# apex-alpha-ii-aaa-version.net
KiCad netlist of a schematic drawn in EAGLE
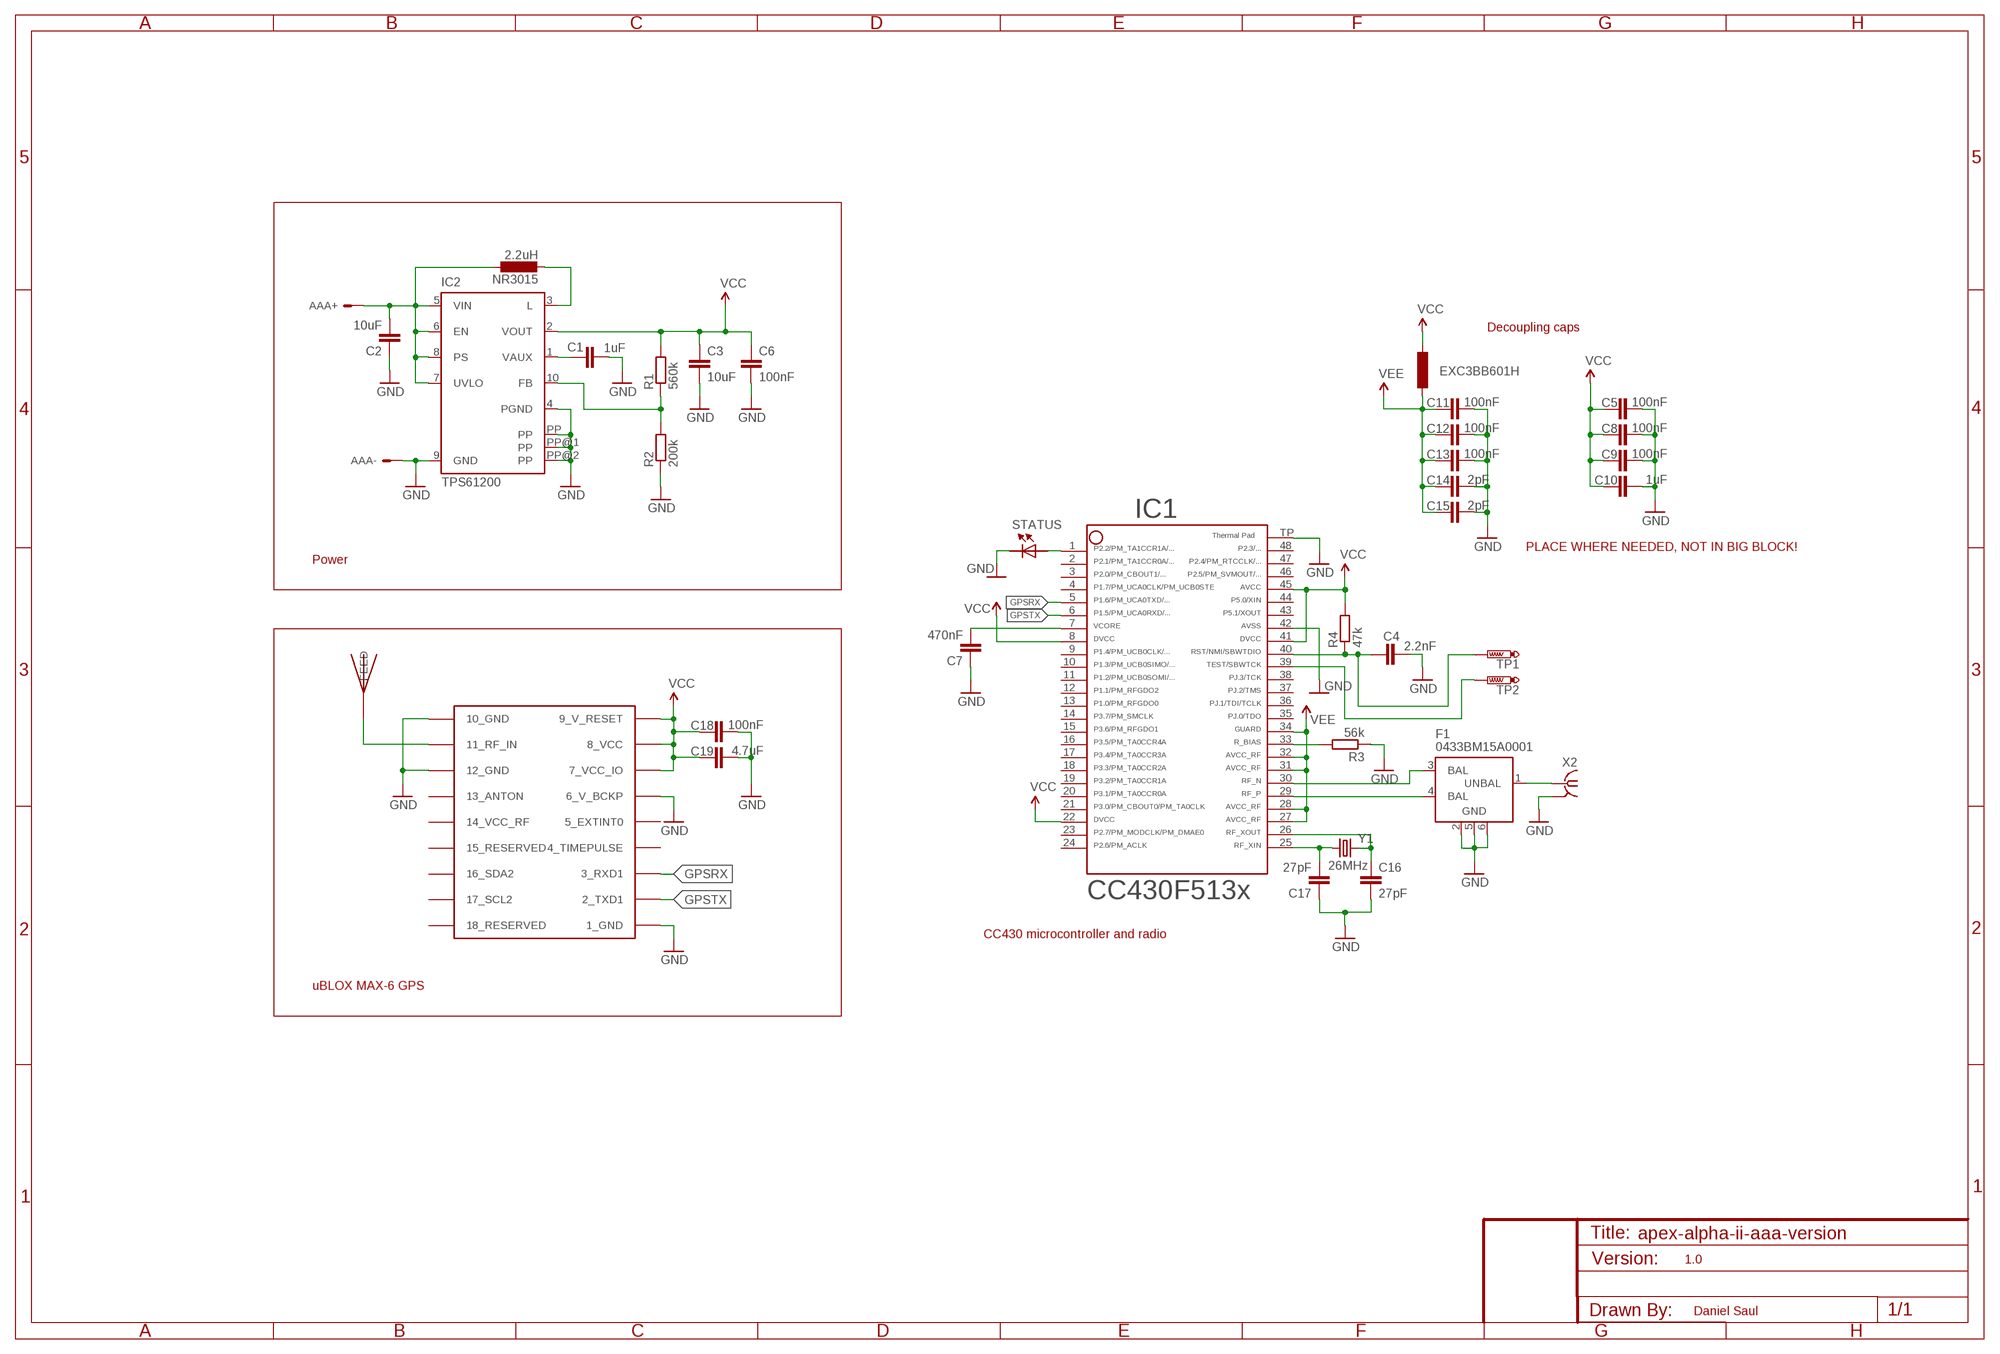
[diagram p0: schematic, sheet 1]

(export (version "E")
  (design (tool "Eeschema 10.0.6"))
  (components
    (comp (ref "AAA")
      (value "KEYSTONE-2466-THROUGH-HOLE-BATTERY-HOLDER-AAA")
      (footprint "eagle-import:THROUGH-HOLE-BATTERY-HOLDER-AAA")
      (libsource (lib "eagle-import") (part "KEYSTONE-2466-THROUGH-HOLE-BATTERY-HOLDER-AAA"))
    )
    (comp (ref "C1")
      (value "1uF")
      (footprint "eagle-import:0402-CAP")
      (libsource (lib "eagle-import") (part "CAP0402-CAP"))
    )
    (comp (ref "C2")
      (value "10uF")
      (footprint "eagle-import:0805")
      (libsource (lib "eagle-import") (part "CAP0805"))
    )
    (comp (ref "C3")
      (value "10uF")
      (footprint "eagle-import:0805")
      (libsource (lib "eagle-import") (part "CAP0805"))
    )
    (comp (ref "C4")
      (value "2.2nF")
      (footprint "eagle-import:0402-CAP")
      (libsource (lib "eagle-import") (part "CAP0402-CAP"))
    )
    (comp (ref "C5")
      (value "100nF")
      (footprint "eagle-import:0402-CAP")
      (libsource (lib "eagle-import") (part "CAP0402-CAP"))
    )
    (comp (ref "C6")
      (value "100nF")
      (footprint "eagle-import:0402-CAP")
      (libsource (lib "eagle-import") (part "CAP0402-CAP"))
    )
    (comp (ref "C7")
      (value "470nF")
      (footprint "eagle-import:0402-CAP")
      (libsource (lib "eagle-import") (part "CAP0402-CAP"))
    )
    (comp (ref "C8")
      (value "100nF")
      (footprint "eagle-import:0402-CAP")
      (libsource (lib "eagle-import") (part "CAP0402-CAP"))
    )
    (comp (ref "C9")
      (value "100nF")
      (footprint "eagle-import:0402-CAP")
      (libsource (lib "eagle-import") (part "CAP0402-CAP"))
    )
    (comp (ref "C10")
      (value "1uF")
      (footprint "eagle-import:0402-CAP")
      (libsource (lib "eagle-import") (part "CAP0402-CAP"))
    )
    (comp (ref "C11")
      (value "100nF")
      (footprint "eagle-import:0402-CAP")
      (libsource (lib "eagle-import") (part "CAP0402-CAP"))
    )
    (comp (ref "C12")
      (value "100nF")
      (footprint "eagle-import:0402-CAP")
      (libsource (lib "eagle-import") (part "CAP0402-CAP"))
    )
    (comp (ref "C13")
      (value "100nF")
      (footprint "eagle-import:0402-CAP")
      (libsource (lib "eagle-import") (part "CAP0402-CAP"))
    )
    (comp (ref "C14")
      (value "2pF")
      (footprint "eagle-import:0402-CAP")
      (libsource (lib "eagle-import") (part "CAP0402-CAP"))
    )
    (comp (ref "C15")
      (value "2pF")
      (footprint "eagle-import:0402-CAP")
      (libsource (lib "eagle-import") (part "CAP0402-CAP"))
    )
    (comp (ref "C16")
      (value "27pF")
      (footprint "eagle-import:0402-CAP")
      (libsource (lib "eagle-import") (part "CAP0402-CAP"))
    )
    (comp (ref "C17")
      (value "27pF")
      (footprint "eagle-import:0402-CAP")
      (libsource (lib "eagle-import") (part "CAP0402-CAP"))
    )
    (comp (ref "C18")
      (value "100nF")
      (footprint "eagle-import:0402-CAP")
      (libsource (lib "eagle-import") (part "CAP0402-CAP"))
    )
    (comp (ref "C19")
      (value "4.7uF")
      (footprint "eagle-import:0805")
      (libsource (lib "eagle-import") (part "CAP0805"))
    )
    (comp (ref "F1")
      (value "0433BM15A0001")
      (footprint "eagle-import:2450BM15A0002")
      (libsource (lib "eagle-import") (part "2450BM15A0002"))
    )
    (comp (ref "GPS")
      (value "UBLOX_MAX-6")
      (footprint "eagle-import:UBLOX_MAX-6")
      (libsource (lib "eagle-import") (part "UBLOX_MAX-6"))
    )
    (comp (ref "IC1")
      (value "CC430F5135")
      (footprint "eagle-import:RGZ48")
      (libsource (lib "eagle-import") (part "CC430F513X---RGZ48"))
    )
    (comp (ref "IC2")
      (value "TPS61200")
      (footprint "eagle-import:S-PDSO-N10")
      (fields (field (name "MPN") "TPS61200DRCT"))
      (libsource (lib "eagle-import") (part "TPS61200"))
    )
    (comp (ref "NR3015")
      (value "2.2uH")
      (footprint "eagle-import:NR3015")
      (libsource (lib "eagle-import") (part "NR3015"))
    )
    (comp (ref "R1")
      (value "560k")
      (footprint "eagle-import:R0402")
      (libsource (lib "eagle-import") (part "R-EU_R0402"))
    )
    (comp (ref "R2")
      (value "200k")
      (footprint "eagle-import:R0402")
      (libsource (lib "eagle-import") (part "R-EU_R0402"))
    )
    (comp (ref "R3")
      (value "56k")
      (footprint "eagle-import:R0402")
      (libsource (lib "eagle-import") (part "R-EU_R0402"))
    )
    (comp (ref "R4")
      (value "47k")
      (footprint "eagle-import:R0402")
      (libsource (lib "eagle-import") (part "R-EU_R0402"))
    )
    (comp (ref "TP1")
      (value "PTR1B1,27")
      (footprint "eagle-import:B1,27")
      (libsource (lib "eagle-import") (part "PTR1B1,27"))
    )
    (comp (ref "TP2")
      (value "PTR1B1,27")
      (footprint "eagle-import:B1,27")
      (libsource (lib "eagle-import") (part "PTR1B1,27"))
    )
    (comp (ref "U$1")
      (value "JTI_ANTENNA-1575AT43A40")
      (footprint "eagle-import:JTI_ANTENNA-1575AT43A40")
      (libsource (lib "eagle-import") (part "JTI_ANTENNA-1575AT43A40"))
    )
    (comp (ref "U$2")
      (value "EXC3BB601H")
      (footprint "eagle-import:R0603")
      (libsource (lib "eagle-import") (part "0603INDUCTOR"))
    )
    (comp (ref "U$3")
      (value "STATUS")
      (footprint "eagle-import:R0402")
      (libsource (lib "eagle-import") (part "LED"))
    )
    (comp (ref "X2")
      (value "SMA-142-0701-801/806")
      (footprint "eagle-import:J502-ND-142-0701-801_806")
      (fields
        (field (name "MF") "JOHNSON COMPONENTS")
        (field (name "MPN") "142-0701-801")
        (field (name "MPN_1") "142-0701-801")
        (field (name "OC_FARNELL") "1608592")
        (field (name "OC_NEWARK") "90F2624")
      )
      (libsource (lib "eagle-import") (part "SMA-142-0701-801/806"))
    )
    (comp (ref "Y1")
      (value "26MHz")
      (footprint "eagle-import:CRYSTAL-SMD-5X3")
      (libsource (lib "eagle-import") (part "CRYSTAL5X3"))
    )
  )
  (nets
    (net (code "1") (name "GND") (class "Default")
      (node (ref "AAA") (pin "GND") (pinfunction "S_GND") (pintype "passive"))
      (node (ref "C1") (pin "2") (pinfunction "2_2") (pintype "passive"))
      (node (ref "C10") (pin "2") (pinfunction "2_2") (pintype "passive"))
      (node (ref "C11") (pin "2") (pinfunction "2_2") (pintype "passive"))
      (node (ref "C12") (pin "2") (pinfunction "2_2") (pintype "passive"))
      (node (ref "C13") (pin "2") (pinfunction "2_2") (pintype "passive"))
      (node (ref "C14") (pin "2") (pinfunction "2_2") (pintype "passive"))
      (node (ref "C15") (pin "2") (pinfunction "2_2") (pintype "passive"))
      (node (ref "C16") (pin "2") (pinfunction "2_2") (pintype "passive"))
      (node (ref "C17") (pin "1") (pinfunction "1_1") (pintype "passive"))
      (node (ref "C18") (pin "2") (pinfunction "2_2") (pintype "passive"))
      (node (ref "C19") (pin "2") (pinfunction "2_2") (pintype "passive"))
      (node (ref "C2") (pin "1") (pinfunction "1_1") (pintype "passive"))
      (node (ref "C3") (pin "2") (pinfunction "2_2") (pintype "passive"))
      (node (ref "C4") (pin "2") (pinfunction "2_2") (pintype "passive"))
      (node (ref "C5") (pin "2") (pinfunction "2_2") (pintype "passive"))
      (node (ref "C6") (pin "2") (pinfunction "2_2") (pintype "passive"))
      (node (ref "C7") (pin "1") (pinfunction "1_1") (pintype "passive"))
      (node (ref "C8") (pin "2") (pinfunction "2_2") (pintype "passive"))
      (node (ref "C9") (pin "2") (pinfunction "2_2") (pintype "passive"))
      (node (ref "F1") (pin "2") (pinfunction "GND_2") (pintype "passive"))
      (node (ref "F1") (pin "5") (pinfunction "GND_5") (pintype "passive"))
      (node (ref "F1") (pin "6") (pinfunction "GND_6") (pintype "passive"))
      (node (ref "GPS") (pin "10_GND") (pinfunction "10_GND_10_GND") (pintype "power_in"))
      (node (ref "GPS") (pin "12_GND") (pinfunction "12_GND_12_GND") (pintype "power_in"))
      (node (ref "GPS") (pin "1_GND") (pinfunction "1_GND_1_GND") (pintype "power_in"))
      (node (ref "GPS") (pin "6_V_BCKP") (pinfunction "6_V_BCKP_6_V_BCKP") (pintype "bidirectional"))
      (node (ref "IC1") (pin "42") (pinfunction "42_42") (pintype "power_in"))
      (node (ref "IC1") (pin "TP") (pinfunction "49_TP") (pintype "power_in"))
      (node (ref "IC2") (pin "4") (pinfunction "PGND_4") (pintype "power_in"))
      (node (ref "IC2") (pin "9") (pinfunction "GND_9") (pintype "power_in"))
      (node (ref "IC2") (pin "PP") (pinfunction "PP_PP") (pintype "power_in"))
      (node (ref "IC2") (pin "PP@1") (pinfunction "PP_PP@1") (pintype "power_in"))
      (node (ref "IC2") (pin "PP@2") (pinfunction "PP_PP@2") (pintype "power_in"))
      (node (ref "R2") (pin "1") (pinfunction "1_1") (pintype "passive"))
      (node (ref "R3") (pin "1") (pinfunction "1_1") (pintype "passive"))
      (node (ref "U$3") (pin "1") (pinfunction "C_1") (pintype "passive"))
      (node (ref "X2") (pin "G@1") (pinfunction "GND_G@1") (pintype "power_in"))
    )
    (net (code "2") (name "GPSRX") (class "Default")
      (node (ref "GPS") (pin "3_RXD1") (pinfunction "3_RXD1_3_RXD1") (pintype "bidirectional"))
      (node (ref "IC1") (pin "5") (pinfunction "5_5") (pintype "bidirectional"))
    )
    (net (code "3") (name "GPSTX") (class "Default")
      (node (ref "GPS") (pin "2_TXD1") (pinfunction "2_TXD1_2_TXD1") (pintype "bidirectional"))
      (node (ref "IC1") (pin "6") (pinfunction "6_6") (pintype "bidirectional"))
    )
    (net (code "4") (name "Net-(AAAA-S)") (class "Default")
      (node (ref "AAA") (pin "+V") (pinfunction "S_+V") (pintype "passive"))
      (node (ref "C2") (pin "2") (pinfunction "2_2") (pintype "passive"))
      (node (ref "IC2") (pin "5") (pinfunction "VIN_5") (pintype "input"))
      (node (ref "IC2") (pin "6") (pinfunction "EN_6") (pintype "input"))
      (node (ref "IC2") (pin "7") (pinfunction "UVLO_7") (pintype "input"))
      (node (ref "IC2") (pin "8") (pinfunction "PS_8") (pintype "input"))
      (node (ref "NR3015") (pin "P$1") (pinfunction "1_P$1") (pintype "passive"))
    )
    (net (code "5") (name "Net-(C4-Pad1)") (class "Default")
      (node (ref "C4") (pin "1") (pinfunction "1_1") (pintype "passive"))
      (node (ref "IC1") (pin "40") (pinfunction "40_40") (pintype "bidirectional"))
      (node (ref "R4") (pin "1") (pinfunction "1_1") (pintype "passive"))
      (node (ref "TP1") (pin "TP") (pinfunction "TP_TP") (pintype "input"))
    )
    (net (code "6") (name "Net-(C7-Pad2)") (class "Default")
      (node (ref "C7") (pin "2") (pinfunction "2_2") (pintype "passive"))
      (node (ref "IC1") (pin "7") (pinfunction "7_7") (pintype "power_in"))
    )
    (net (code "7") (name "Net-(C17-Pad2)") (class "Default")
      (node (ref "C17") (pin "2") (pinfunction "2_2") (pintype "passive"))
      (node (ref "IC1") (pin "25") (pinfunction "25_25") (pintype "input"))
      (node (ref "Y1") (pin "1") (pinfunction "1_1") (pintype "passive"))
    )
    (net (code "8") (name "Net-(F1-BAL-Pad3)") (class "Default")
      (node (ref "F1") (pin "3") (pinfunction "BAL_3") (pintype "passive"))
      (node (ref "IC1") (pin "30") (pinfunction "30_30") (pintype "bidirectional"))
    )
    (net (code "9") (name "Net-(F1-BAL-Pad4)") (class "Default")
      (node (ref "F1") (pin "4") (pinfunction "BAL_4") (pintype "passive"))
      (node (ref "IC1") (pin "29") (pinfunction "29_29") (pintype "bidirectional"))
    )
    (net (code "10") (name "Net-(F1-UNBAL)") (class "Default")
      (node (ref "F1") (pin "1") (pinfunction "UNBAL_1") (pintype "passive"))
      (node (ref "X2") (pin "1") (pinfunction "1_1") (pintype "passive"))
    )
    (net (code "11") (name "Net-(GPS-Pad11_RF_IN)") (class "Default")
      (node (ref "GPS") (pin "11_RF_IN") (pinfunction "11_RF_IN_11_RF_IN") (pintype "bidirectional"))
      (node (ref "U$1") (pin "FEED") (pinfunction "FEED_FEED") (pintype "bidirectional"))
    )
    (net (code "12") (name "Net-(IC1-Pad33)") (class "Default")
      (node (ref "IC1") (pin "33") (pinfunction "33_33") (pintype "power_in"))
      (node (ref "R3") (pin "2") (pinfunction "2_2") (pintype "passive"))
    )
    (net (code "13") (name "Net-(IC1-Pad39)") (class "Default")
      (node (ref "IC1") (pin "39") (pinfunction "39_39") (pintype "input"))
      (node (ref "TP2") (pin "TP") (pinfunction "TP_TP") (pintype "input"))
    )
    (net (code "14") (name "Net-(IC2-FB)") (class "Default")
      (node (ref "IC2") (pin "10") (pinfunction "FB_10") (pintype "input"))
      (node (ref "R1") (pin "1") (pinfunction "1_1") (pintype "passive"))
      (node (ref "R2") (pin "2") (pinfunction "2_2") (pintype "passive"))
    )
    (net (code "15") (name "Net-(IC2-L)") (class "Default")
      (node (ref "IC2") (pin "3") (pinfunction "L_3") (pintype "input"))
      (node (ref "NR3015") (pin "P$2") (pinfunction "2_P$2") (pintype "passive"))
    )
    (net (code "16") (name "Net-(IC2-VAUX)") (class "Default")
      (node (ref "C1") (pin "1") (pinfunction "1_1") (pintype "passive"))
      (node (ref "IC2") (pin "1") (pinfunction "VAUX_1") (pintype "bidirectional"))
    )
    (net (code "17") (name "Net-(U$3-A)") (class "Default")
      (node (ref "IC1") (pin "1") (pinfunction "1_1") (pintype "bidirectional"))
      (node (ref "U$3") (pin "2") (pinfunction "A_2") (pintype "passive"))
    )
    (net (code "18") (name "Net-(Y1-2)") (class "Default")
      (node (ref "C16") (pin "1") (pinfunction "1_1") (pintype "passive"))
      (node (ref "IC1") (pin "26") (pinfunction "26_26") (pintype "output"))
      (node (ref "Y1") (pin "3") (pinfunction "2_3") (pintype "passive"))
    )
    (net (code "19") (name "VCC") (class "Default")
      (node (ref "C10") (pin "1") (pinfunction "1_1") (pintype "passive"))
      (node (ref "C18") (pin "1") (pinfunction "1_1") (pintype "passive"))
      (node (ref "C19") (pin "1") (pinfunction "1_1") (pintype "passive"))
      (node (ref "C3") (pin "1") (pinfunction "1_1") (pintype "passive"))
      (node (ref "C5") (pin "1") (pinfunction "1_1") (pintype "passive"))
      (node (ref "C6") (pin "1") (pinfunction "1_1") (pintype "passive"))
      (node (ref "C8") (pin "1") (pinfunction "1_1") (pintype "passive"))
      (node (ref "C9") (pin "1") (pinfunction "1_1") (pintype "passive"))
      (node (ref "GPS") (pin "7_VCC_IO") (pinfunction "7_VCC_IO_7_VCC_IO") (pintype "power_in"))
      (node (ref "GPS") (pin "8_VCC") (pinfunction "8_VCC_8_VCC") (pintype "power_in"))
      (node (ref "GPS") (pin "9_V_RESET") (pinfunction "9_V_RESET_9_V_RESET") (pintype "power_in"))
      (node (ref "IC1") (pin "22") (pinfunction "22_22") (pintype "power_in"))
      (node (ref "IC1") (pin "41") (pinfunction "41_41") (pintype "power_in"))
      (node (ref "IC1") (pin "45") (pinfunction "45_45") (pintype "input"))
      (node (ref "IC1") (pin "8") (pinfunction "8_8") (pintype "power_in"))
      (node (ref "IC2") (pin "2") (pinfunction "VOUT_2") (pintype "passive"))
      (node (ref "R1") (pin "2") (pinfunction "2_2") (pintype "passive"))
      (node (ref "R4") (pin "2") (pinfunction "2_2") (pintype "passive"))
      (node (ref "U$2") (pin "1") (pinfunction "1_1") (pintype "passive"))
    )
    (net (code "20") (name "VEE") (class "Default")
      (node (ref "C11") (pin "1") (pinfunction "1_1") (pintype "passive"))
      (node (ref "C12") (pin "1") (pinfunction "1_1") (pintype "passive"))
      (node (ref "C13") (pin "1") (pinfunction "1_1") (pintype "passive"))
      (node (ref "C14") (pin "1") (pinfunction "1_1") (pintype "passive"))
      (node (ref "C15") (pin "1") (pinfunction "1_1") (pintype "passive"))
      (node (ref "IC1") (pin "27") (pinfunction "27_27") (pintype "power_in"))
      (node (ref "IC1") (pin "28") (pinfunction "28_28") (pintype "bidirectional"))
      (node (ref "IC1") (pin "31") (pinfunction "31_31") (pintype "power_in"))
      (node (ref "IC1") (pin "32") (pinfunction "32_32") (pintype "power_in"))
      (node (ref "IC1") (pin "34") (pinfunction "34_34") (pintype "power_in"))
      (node (ref "U$2") (pin "2") (pinfunction "2_2") (pintype "passive"))
    )
    (net (code "21") (name "unconnected-(GPS-Pad4_TIMEPULSE)") (class "Default")
      (node (ref "GPS") (pin "4_TIMEPULSE") (pinfunction "4_TIMEPULSE_4_TIMEPULSE") (pintype "bidirectional"))
    )
    (net (code "22") (name "unconnected-(GPS-Pad5_EXTINT0)") (class "Default")
      (node (ref "GPS") (pin "5_EXTINT0") (pinfunction "5_EXTINT0_5_EXTINT0") (pintype "bidirectional"))
    )
    (net (code "23") (name "unconnected-(GPS-Pad13_ANTON)") (class "Default")
      (node (ref "GPS") (pin "13_ANTON") (pinfunction "13_ANTON_13_ANTON") (pintype "bidirectional"))
    )
    (net (code "24") (name "unconnected-(GPS-Pad14_VCC_RF)") (class "Default")
      (node (ref "GPS") (pin "14_VCC_RF") (pinfunction "14_VCC_RF_14_VCC_RF") (pintype "bidirectional"))
    )
    (net (code "25") (name "unconnected-(GPS-Pad15_RESERVED)") (class "Default")
      (node (ref "GPS") (pin "15_RESERVED") (pinfunction "15_RESERVED_15_RESERVED") (pintype "bidirectional"))
    )
    (net (code "26") (name "unconnected-(GPS-Pad16_SDA2)") (class "Default")
      (node (ref "GPS") (pin "16_SDA2") (pinfunction "16_SDA2_16_SDA2") (pintype "bidirectional"))
    )
    (net (code "27") (name "unconnected-(GPS-Pad17_SCL2)") (class "Default")
      (node (ref "GPS") (pin "17_SCL2") (pinfunction "17_SCL2_17_SCL2") (pintype "bidirectional"))
    )
    (net (code "28") (name "unconnected-(GPS-Pad18_RESERVED)") (class "Default")
      (node (ref "GPS") (pin "18_RESERVED") (pinfunction "18_RESERVED_18_RESERVED") (pintype "bidirectional"))
    )
    (net (code "29") (name "unconnected-(IC1-Pad2)") (class "Default")
      (node (ref "IC1") (pin "2") (pinfunction "2_2") (pintype "bidirectional"))
    )
    (net (code "30") (name "unconnected-(IC1-Pad3)") (class "Default")
      (node (ref "IC1") (pin "3") (pinfunction "3_3") (pintype "bidirectional"))
    )
    (net (code "31") (name "unconnected-(IC1-Pad4)") (class "Default")
      (node (ref "IC1") (pin "4") (pinfunction "4_4") (pintype "bidirectional"))
    )
    (net (code "32") (name "unconnected-(IC1-Pad9)") (class "Default")
      (node (ref "IC1") (pin "9") (pinfunction "9_9") (pintype "bidirectional"))
    )
    (net (code "33") (name "unconnected-(IC1-Pad10)") (class "Default")
      (node (ref "IC1") (pin "10") (pinfunction "10_10") (pintype "bidirectional"))
    )
    (net (code "34") (name "unconnected-(IC1-Pad11)") (class "Default")
      (node (ref "IC1") (pin "11") (pinfunction "11_11") (pintype "bidirectional"))
    )
    (net (code "35") (name "unconnected-(IC1-Pad12)") (class "Default")
      (node (ref "IC1") (pin "12") (pinfunction "12_12") (pintype "bidirectional"))
    )
    (net (code "36") (name "unconnected-(IC1-Pad13)") (class "Default")
      (node (ref "IC1") (pin "13") (pinfunction "13_13") (pintype "bidirectional"))
    )
    (net (code "37") (name "unconnected-(IC1-Pad14)") (class "Default")
      (node (ref "IC1") (pin "14") (pinfunction "14_14") (pintype "bidirectional"))
    )
    (net (code "38") (name "unconnected-(IC1-Pad15)") (class "Default")
      (node (ref "IC1") (pin "15") (pinfunction "15_15") (pintype "bidirectional"))
    )
    (net (code "39") (name "unconnected-(IC1-Pad16)") (class "Default")
      (node (ref "IC1") (pin "16") (pinfunction "16_16") (pintype "bidirectional"))
    )
    (net (code "40") (name "unconnected-(IC1-Pad17)") (class "Default")
      (node (ref "IC1") (pin "17") (pinfunction "17_17") (pintype "bidirectional"))
    )
    (net (code "41") (name "unconnected-(IC1-Pad18)") (class "Default")
      (node (ref "IC1") (pin "18") (pinfunction "18_18") (pintype "bidirectional"))
    )
    (net (code "42") (name "unconnected-(IC1-Pad19)") (class "Default")
      (node (ref "IC1") (pin "19") (pinfunction "19_19") (pintype "bidirectional"))
    )
    (net (code "43") (name "unconnected-(IC1-Pad20)") (class "Default")
      (node (ref "IC1") (pin "20") (pinfunction "20_20") (pintype "bidirectional"))
    )
    (net (code "44") (name "unconnected-(IC1-Pad21)") (class "Default")
      (node (ref "IC1") (pin "21") (pinfunction "21_21") (pintype "bidirectional"))
    )
    (net (code "45") (name "unconnected-(IC1-Pad23)") (class "Default")
      (node (ref "IC1") (pin "23") (pinfunction "23_23") (pintype "bidirectional"))
    )
    (net (code "46") (name "unconnected-(IC1-Pad24)") (class "Default")
      (node (ref "IC1") (pin "24") (pinfunction "24_24") (pintype "bidirectional"))
    )
    (net (code "47") (name "unconnected-(IC1-Pad35)") (class "Default")
      (node (ref "IC1") (pin "35") (pinfunction "35_35") (pintype "bidirectional"))
    )
    (net (code "48") (name "unconnected-(IC1-Pad36)") (class "Default")
      (node (ref "IC1") (pin "36") (pinfunction "36_36") (pintype "bidirectional"))
    )
    (net (code "49") (name "unconnected-(IC1-Pad37)") (class "Default")
      (node (ref "IC1") (pin "37") (pinfunction "37_37") (pintype "bidirectional"))
    )
    (net (code "50") (name "unconnected-(IC1-Pad38)") (class "Default")
      (node (ref "IC1") (pin "38") (pinfunction "38_38") (pintype "bidirectional"))
    )
    (net (code "51") (name "unconnected-(IC1-Pad43)") (class "Default")
      (node (ref "IC1") (pin "43") (pinfunction "43_43") (pintype "input"))
    )
    (net (code "52") (name "unconnected-(IC1-Pad44)") (class "Default")
      (node (ref "IC1") (pin "44") (pinfunction "44_44") (pintype "input"))
    )
    (net (code "53") (name "unconnected-(IC1-Pad46)") (class "Default")
      (node (ref "IC1") (pin "46") (pinfunction "46_46") (pintype "bidirectional"))
    )
    (net (code "54") (name "unconnected-(IC1-Pad47)") (class "Default")
      (node (ref "IC1") (pin "47") (pinfunction "47_47") (pintype "input"))
    )
    (net (code "55") (name "unconnected-(IC1-Pad48)") (class "Default")
      (node (ref "IC1") (pin "48") (pinfunction "48_48") (pintype "bidirectional"))
    )
  )
)
